# vA-ESP32.net
KiCad netlist of a schematic drawn in EAGLE
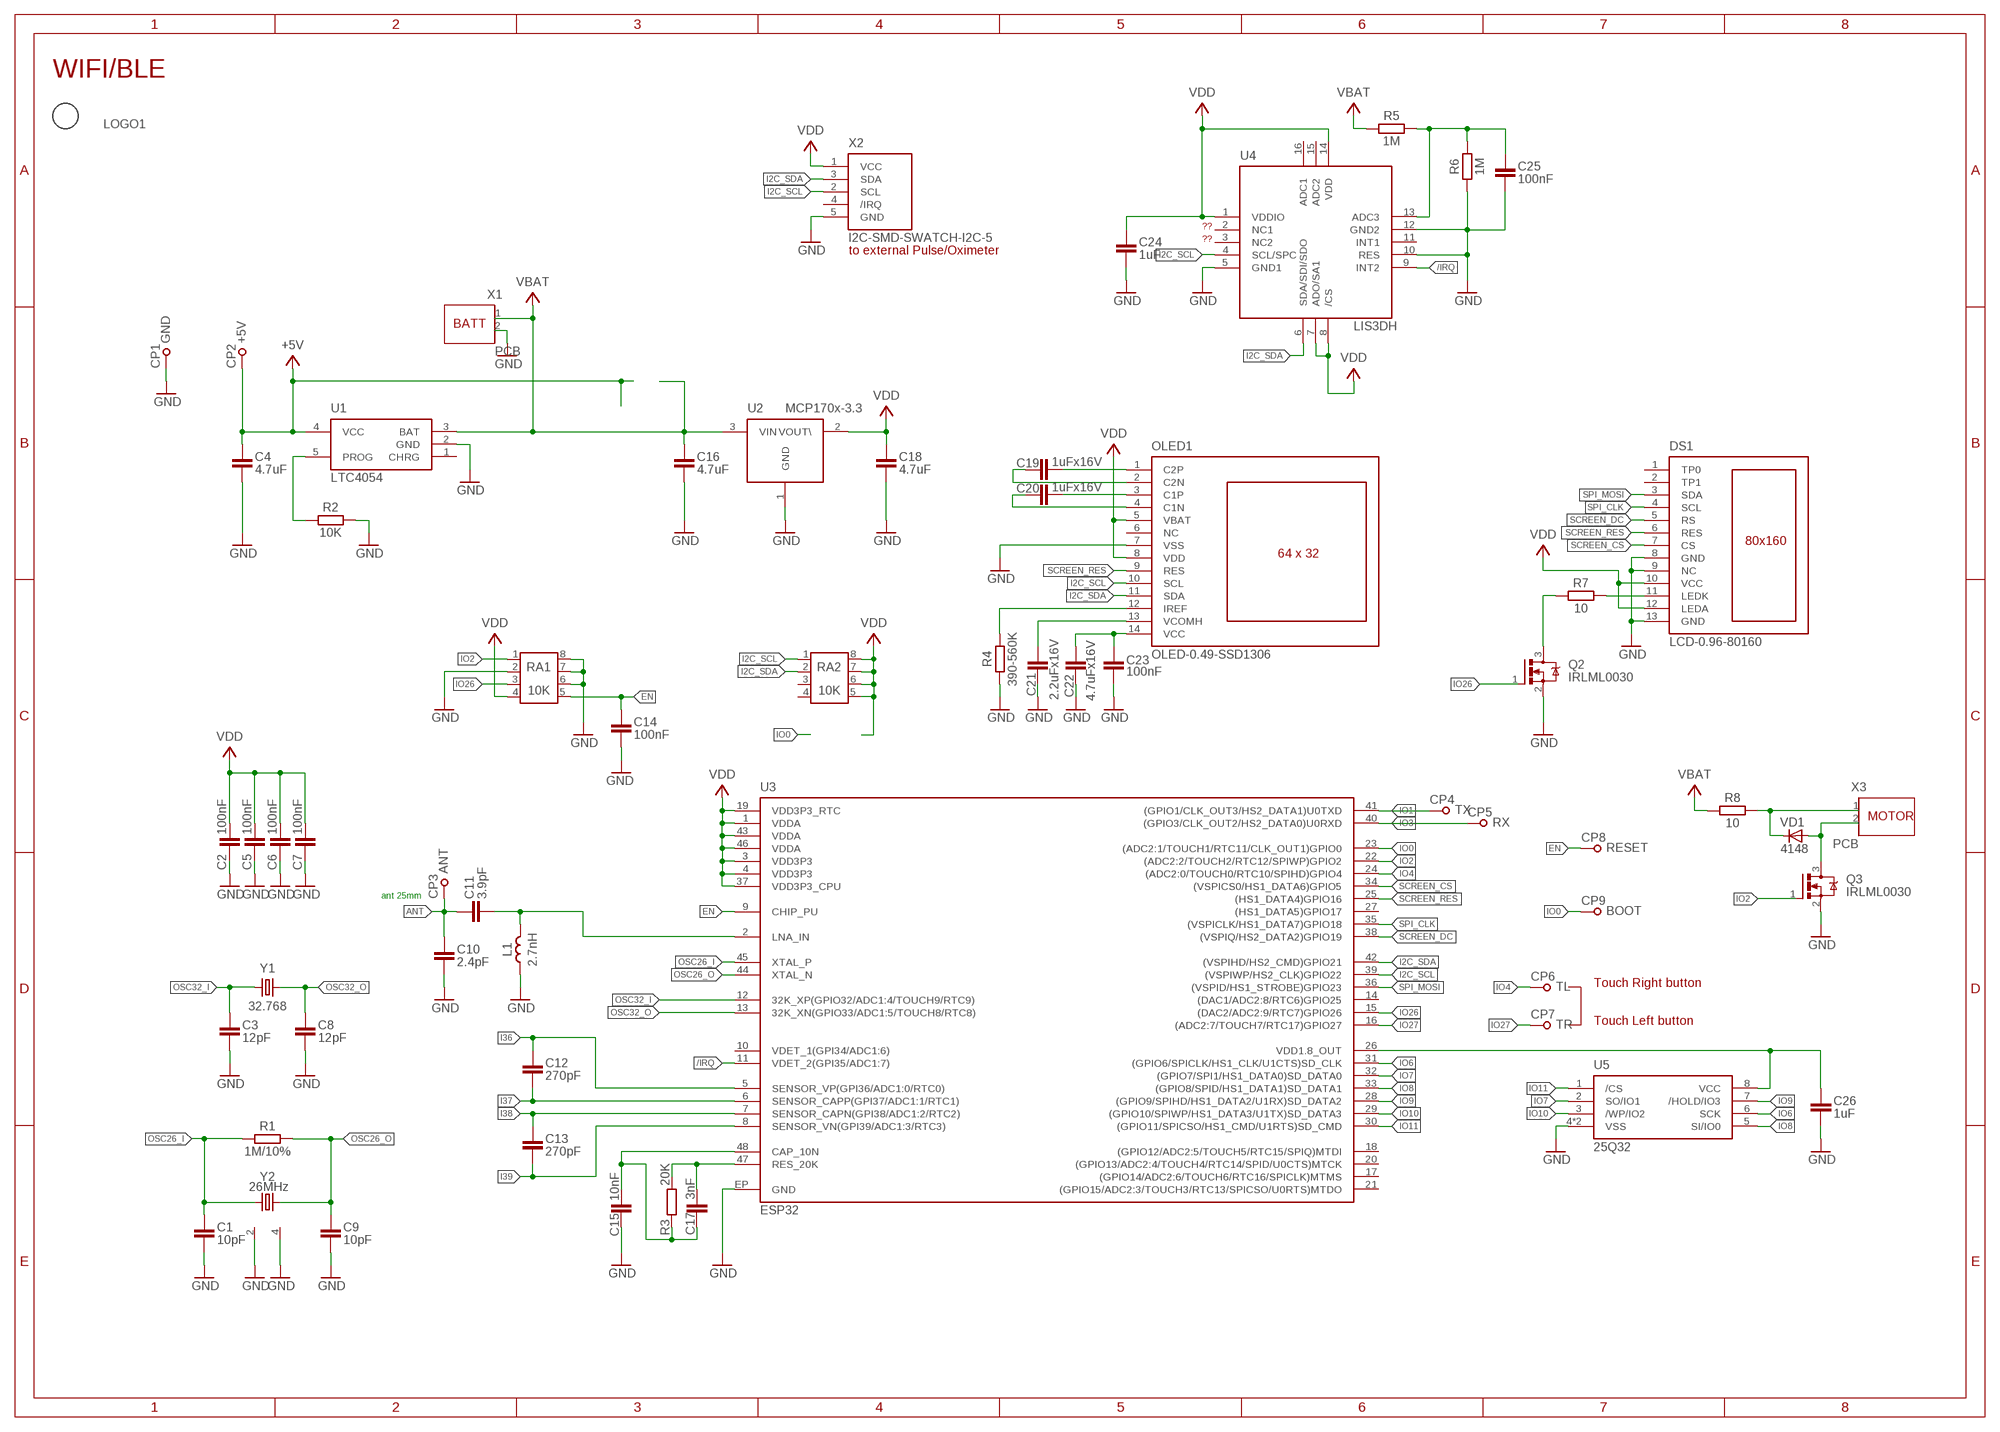
[diagram p0: schematic, sheet 1]

(export (version "E")
  (design (tool "Eeschema 10.0.6"))
  (components
    (comp (ref "C1")
      (value "10pF")
      (footprint "eagle-import:C0402")
      (libsource (lib "eagle-import") (part "C-EU-C0402"))
    )
    (comp (ref "C2")
      (value "100nF")
      (footprint "eagle-import:C0402")
      (libsource (lib "eagle-import") (part "C-EU-C0402"))
    )
    (comp (ref "C3")
      (value "12pF")
      (footprint "eagle-import:C0402")
      (libsource (lib "eagle-import") (part "C-EU-C0402"))
    )
    (comp (ref "C4")
      (value "4.7uF")
      (footprint "eagle-import:C0603")
      (libsource (lib "eagle-import") (part "C-EU-C0603"))
    )
    (comp (ref "C5")
      (value "100nF")
      (footprint "eagle-import:C0603")
      (libsource (lib "eagle-import") (part "C-EU-C0603"))
    )
    (comp (ref "C6")
      (value "100nF")
      (footprint "eagle-import:C0402")
      (libsource (lib "eagle-import") (part "C-EU-C0402"))
    )
    (comp (ref "C7")
      (value "100nF")
      (footprint "eagle-import:C0402")
      (libsource (lib "eagle-import") (part "C-EU-C0402"))
    )
    (comp (ref "C8")
      (value "12pF")
      (footprint "eagle-import:C0402")
      (libsource (lib "eagle-import") (part "C-EU-C0402"))
    )
    (comp (ref "C9")
      (value "10pF")
      (footprint "eagle-import:C0402")
      (libsource (lib "eagle-import") (part "C-EU-C0402"))
    )
    (comp (ref "C10")
      (value "2.4pF")
      (footprint "eagle-import:C0402")
      (libsource (lib "eagle-import") (part "C-EU-C0402"))
    )
    (comp (ref "C11")
      (value "3.9pF")
      (footprint "eagle-import:C0402")
      (libsource (lib "eagle-import") (part "C-EU-C0402"))
    )
    (comp (ref "C12")
      (value "270pF")
      (footprint "eagle-import:C0402")
      (libsource (lib "eagle-import") (part "C-EU-C0402"))
    )
    (comp (ref "C13")
      (value "270pF")
      (footprint "eagle-import:C0402")
      (libsource (lib "eagle-import") (part "C-EU-C0402"))
    )
    (comp (ref "C14")
      (value "100nF")
      (footprint "eagle-import:C0402")
      (libsource (lib "eagle-import") (part "C-EU-C0402"))
    )
    (comp (ref "C15")
      (value "10nF")
      (footprint "eagle-import:C0402")
      (libsource (lib "eagle-import") (part "C-EU-C0402"))
    )
    (comp (ref "C16")
      (value "4.7uF")
      (footprint "eagle-import:C0603")
      (libsource (lib "eagle-import") (part "C-EU-C0603"))
    )
    (comp (ref "C17")
      (value "3nF")
      (footprint "eagle-import:C0402")
      (libsource (lib "eagle-import") (part "C-EU-C0402"))
    )
    (comp (ref "C18")
      (value "4.7uF")
      (footprint "eagle-import:C0603")
      (libsource (lib "eagle-import") (part "C-EU-C0603"))
    )
    (comp (ref "C19")
      (value "1uFx16V")
      (footprint "eagle-import:C0603")
      (libsource (lib "eagle-import") (part "C-EU-C0603"))
    )
    (comp (ref "C20")
      (value "1uFx16V")
      (footprint "eagle-import:C0603")
      (libsource (lib "eagle-import") (part "C-EU-C0603"))
    )
    (comp (ref "C21")
      (value "2.2uFx16V")
      (footprint "eagle-import:C0805")
      (libsource (lib "eagle-import") (part "C-EU-C0805"))
    )
    (comp (ref "C22")
      (value "4.7uFx16V")
      (footprint "eagle-import:C0805")
      (libsource (lib "eagle-import") (part "C-EU-C0805"))
    )
    (comp (ref "C23")
      (value "100nF")
      (footprint "eagle-import:C0603")
      (libsource (lib "eagle-import") (part "C-EU-C0603"))
    )
    (comp (ref "C24")
      (value "1uF")
      (footprint "eagle-import:C0402")
      (libsource (lib "eagle-import") (part "C-EU-C0402"))
    )
    (comp (ref "C25")
      (value "100nF")
      (footprint "eagle-import:C0402")
      (libsource (lib "eagle-import") (part "C-EU-C0402"))
    )
    (comp (ref "C26")
      (value "1uF")
      (footprint "eagle-import:C0603")
      (libsource (lib "eagle-import") (part "C-EU-C0603"))
    )
    (comp (ref "CP1")
      (value "GND")
      (footprint "eagle-import:CP-1-R08MM")
      (libsource (lib "eagle-import") (part "CP-1"))
    )
    (comp (ref "CP2")
      (value "+5V")
      (footprint "eagle-import:CP-1-R08MM")
      (libsource (lib "eagle-import") (part "CP-1"))
    )
    (comp (ref "CP3")
      (value "ANT")
      (footprint "eagle-import:CP-1-C08MM")
      (libsource (lib "eagle-import") (part "CP"))
    )
    (comp (ref "CP4")
      (value "TX")
      (footprint "eagle-import:CP-1-C08MM")
      (libsource (lib "eagle-import") (part "CP"))
    )
    (comp (ref "CP5")
      (value "RX")
      (footprint "eagle-import:CP-1-C08MM")
      (libsource (lib "eagle-import") (part "CP"))
    )
    (comp (ref "CP6")
      (value "TL")
      (footprint "eagle-import:CP-1-C24MM")
      (libsource (lib "eagle-import") (part "CP-CP-1-C25"))
    )
    (comp (ref "CP7")
      (value "TR")
      (footprint "eagle-import:CP-1-C24MM")
      (libsource (lib "eagle-import") (part "CP-CP-1-C25"))
    )
    (comp (ref "CP8")
      (value "RESET")
      (footprint "eagle-import:CP-1-C08MM")
      (libsource (lib "eagle-import") (part "CP"))
    )
    (comp (ref "CP9")
      (value "BOOT")
      (footprint "eagle-import:CP-1-C08MM")
      (libsource (lib "eagle-import") (part "CP"))
    )
    (comp (ref "DS1")
      (value "LCD-0.96-80160")
      (footprint "eagle-import:LCD-0.96-80_160")
      (libsource (lib "eagle-import") (part "LCD-0.96-80160"))
    )
    (comp (ref "FIDUCIAL1")
      (value "FIDUCIAL-MICRO")
      (footprint "eagle-import:FIDUCIAL-MICRO")
      (libsource (lib "eagle-import") (part "FIDUCIAL-MICRO"))
    )
    (comp (ref "L1")
      (value "2.7nH")
      (footprint "eagle-import:L0402")
      (libsource (lib "eagle-import") (part "LL0402"))
    )
    (comp (ref "LOGO1")
      (value "LOGO6")
      (footprint "eagle-import:LOGO_OMEGA")
      (libsource (lib "eagle-import") (part "LOGO6"))
    )
    (comp (ref "OLED1")
      (value "OLED-0.49-SSD1306")
      (footprint "eagle-import:OLED_0.49-SSD1306")
      (libsource (lib "eagle-import") (part "OLED-0.49-SSD1306"))
    )
    (comp (ref "Q2")
      (value "IRLML0030")
      (footprint "eagle-import:SOT23-3-1")
      (libsource (lib "eagle-import") (part "FET_NSOT23"))
    )
    (comp (ref "Q3")
      (value "IRLML0030")
      (footprint "eagle-import:SOT23-3-1")
      (libsource (lib "eagle-import") (part "FET_NSOT23"))
    )
    (comp (ref "R1")
      (value "1M/10%")
      (footprint "eagle-import:R0402")
      (libsource (lib "eagle-import") (part "R-EU0402"))
    )
    (comp (ref "R2")
      (value "10K")
      (footprint "eagle-import:R0402")
      (libsource (lib "eagle-import") (part "R-EU0402"))
    )
    (comp (ref "R3")
      (value "20K")
      (footprint "eagle-import:R0402")
      (libsource (lib "eagle-import") (part "R-EU0402"))
    )
    (comp (ref "R4")
      (value "390-560K")
      (footprint "eagle-import:R0603")
      (libsource (lib "eagle-import") (part "R-EU0603"))
    )
    (comp (ref "R5")
      (value "1M")
      (footprint "eagle-import:R0402")
      (libsource (lib "eagle-import") (part "R-EU0402"))
    )
    (comp (ref "R6")
      (value "1M")
      (footprint "eagle-import:R0402")
      (libsource (lib "eagle-import") (part "R-EU0402"))
    )
    (comp (ref "R7")
      (value "10")
      (footprint "eagle-import:R0603")
      (libsource (lib "eagle-import") (part "R-EU0603"))
    )
    (comp (ref "R8")
      (value "10")
      (footprint "eagle-import:R0603")
      (libsource (lib "eagle-import") (part "R-EU0603"))
    )
    (comp (ref "RA1")
      (value "10K")
      (footprint "eagle-import:EXB28V")
      (libsource (lib "eagle-import") (part "R-ARRAY-4X0402"))
    )
    (comp (ref "RA2")
      (value "10K")
      (footprint "eagle-import:EXB28V")
      (libsource (lib "eagle-import") (part "R-ARRAY-4X0402"))
    )
    (comp (ref "U1")
      (value "LTC4054")
      (footprint "eagle-import:SOT23-5L")
      (libsource (lib "eagle-import") (part "LTC4054"))
    )
    (comp (ref "U2")
      (value "MCP170x-3.3")
      (footprint "eagle-import:SOT23-3")
      (libsource (lib "eagle-import") (part "MCP170XSOT23"))
    )
    (comp (ref "U3")
      (value "ESP32")
      (footprint "eagle-import:QFN48-6X6-0.4MM")
      (libsource (lib "eagle-import") (part "ESP32"))
    )
    (comp (ref "U4")
      (value "LIS3DH")
      (footprint "eagle-import:LGA16")
      (libsource (lib "eagle-import") (part "LIS3DH"))
    )
    (comp (ref "U5")
      (value "25Q32")
      (footprint "eagle-import:USON-8-2X3")
      (libsource (lib "eagle-import") (part "25CXX-USON8-2X3"))
    )
    (comp (ref "VD1")
      (value "4148")
      (footprint "eagle-import:SOD523")
      (libsource (lib "eagle-import") (part "DIODESOD523"))
    )
    (comp (ref "X1")
      (value "PCB")
      (footprint "eagle-import:2C_SMD-SWATCH")
      (libsource (lib "eagle-import") (part "CON-2PSMD-2"))
    )
    (comp (ref "X2")
      (value "I2C-SMD-SWATCH-I2C-5")
      (footprint "eagle-import:SMD-SWATCH-I2C-5")
      (libsource (lib "eagle-import") (part "I2C-SMD-SWATCH-I2C-5"))
    )
    (comp (ref "X3")
      (value "PCB")
      (footprint "eagle-import:2C_SMD-SWATCH")
      (libsource (lib "eagle-import") (part "CON-2PSMD-2"))
    )
    (comp (ref "Y1")
      (value "32.768")
      (footprint "eagle-import:XTAL3215")
      (libsource (lib "eagle-import") (part "REZONATOR-2PIN3215"))
    )
    (comp (ref "Y2")
      (value "26MHz")
      (footprint "eagle-import:CRYSTAL-SMD-3225")
      (libsource (lib "eagle-import") (part "REZONATOR-4PIN-3225"))
    )
  )
  (nets
    (net (code "1") (name "+5V") (class "Default")
      (node (ref "C4") (pin "1") (pinfunction "1_1") (pintype "passive"))
      (node (ref "CP2") (pin "1") (pinfunction "C1_1") (pintype "bidirectional"))
      (node (ref "U1") (pin "4") (pinfunction "VCC_4") (pintype "bidirectional"))
    )
    (net (code "2") (name "ANT") (class "Default")
      (node (ref "C10") (pin "1") (pinfunction "1_1") (pintype "passive"))
      (node (ref "C11") (pin "1") (pinfunction "1_1") (pintype "passive"))
      (node (ref "CP3") (pin "1") (pinfunction "C1_1") (pintype "bidirectional"))
    )
    (net (code "3") (name "EN") (class "Default")
      (node (ref "C14") (pin "1") (pinfunction "1_1") (pintype "passive"))
      (node (ref "CP8") (pin "1") (pinfunction "C1_1") (pintype "bidirectional"))
      (node (ref "RA1") (pin "5") (pinfunction "5_5") (pintype "passive"))
      (node (ref "U3") (pin "9") (pinfunction "CHIP_PU_9") (pintype "bidirectional"))
    )
    (net (code "4") (name "GND") (class "Default")
      (node (ref "C1") (pin "2") (pinfunction "2_2") (pintype "passive"))
      (node (ref "C10") (pin "2") (pinfunction "2_2") (pintype "passive"))
      (node (ref "C14") (pin "2") (pinfunction "2_2") (pintype "passive"))
      (node (ref "C15") (pin "2") (pinfunction "2_2") (pintype "passive"))
      (node (ref "C16") (pin "2") (pinfunction "2_2") (pintype "passive"))
      (node (ref "C18") (pin "2") (pinfunction "2_2") (pintype "passive"))
      (node (ref "C2") (pin "2") (pinfunction "2_2") (pintype "passive"))
      (node (ref "C21") (pin "2") (pinfunction "2_2") (pintype "passive"))
      (node (ref "C22") (pin "2") (pinfunction "2_2") (pintype "passive"))
      (node (ref "C23") (pin "2") (pinfunction "2_2") (pintype "passive"))
      (node (ref "C24") (pin "2") (pinfunction "2_2") (pintype "passive"))
      (node (ref "C25") (pin "2") (pinfunction "2_2") (pintype "passive"))
      (node (ref "C26") (pin "2") (pinfunction "2_2") (pintype "passive"))
      (node (ref "C3") (pin "2") (pinfunction "2_2") (pintype "passive"))
      (node (ref "C4") (pin "2") (pinfunction "2_2") (pintype "passive"))
      (node (ref "C5") (pin "2") (pinfunction "2_2") (pintype "passive"))
      (node (ref "C6") (pin "2") (pinfunction "2_2") (pintype "passive"))
      (node (ref "C7") (pin "2") (pinfunction "2_2") (pintype "passive"))
      (node (ref "C8") (pin "2") (pinfunction "2_2") (pintype "passive"))
      (node (ref "C9") (pin "2") (pinfunction "2_2") (pintype "passive"))
      (node (ref "CP1") (pin "1") (pinfunction "C1_1") (pintype "bidirectional"))
      (node (ref "DS1") (pin "13") (pinfunction "GND_13") (pintype "bidirectional"))
      (node (ref "DS1") (pin "8") (pinfunction "GND_8") (pintype "bidirectional"))
      (node (ref "DS1") (pin "9") (pinfunction "NC_9") (pintype "bidirectional"))
      (node (ref "L1") (pin "1") (pinfunction "%1_1") (pintype "bidirectional"))
      (node (ref "OLED1") (pin "7") (pinfunction "VSS_7") (pintype "bidirectional"))
      (node (ref "Q2") (pin "2") (pinfunction "S_2") (pintype "passive"))
      (node (ref "Q3") (pin "2") (pinfunction "S_2") (pintype "passive"))
      (node (ref "R2") (pin "2") (pinfunction "2_2") (pintype "passive"))
      (node (ref "R4") (pin "1") (pinfunction "1_1") (pintype "passive"))
      (node (ref "R6") (pin "1") (pinfunction "1_1") (pintype "passive"))
      (node (ref "RA1") (pin "2") (pinfunction "2_2") (pintype "passive"))
      (node (ref "RA1") (pin "6") (pinfunction "6_6") (pintype "passive"))
      (node (ref "RA1") (pin "7") (pinfunction "7_7") (pintype "passive"))
      (node (ref "RA1") (pin "8") (pinfunction "8_8") (pintype "passive"))
      (node (ref "U1") (pin "2") (pinfunction "GND_2") (pintype "bidirectional"))
      (node (ref "U2") (pin "1") (pinfunction "GND_1") (pintype "bidirectional"))
      (node (ref "U3") (pin "EP") (pinfunction "GND_EP") (pintype "bidirectional"))
      (node (ref "U4") (pin "10") (pinfunction "RES_10") (pintype "bidirectional"))
      (node (ref "U4") (pin "12") (pinfunction "GND2_12") (pintype "bidirectional"))
      (node (ref "U4") (pin "5") (pinfunction "GND1_5") (pintype "bidirectional"))
      (node (ref "U5") (pin "4") (pinfunction "VSS_4") (pintype "bidirectional"))
      (node (ref "U5") (pin "P$1") (pinfunction "VSS_P$1") (pintype "bidirectional"))
      (node (ref "X1") (pin "2") (pinfunction "2_2") (pintype "bidirectional"))
      (node (ref "X2") (pin "5") (pinfunction "GND_5") (pintype "bidirectional"))
      (node (ref "Y2") (pin "2") (pinfunction "S_2") (pintype "bidirectional"))
      (node (ref "Y2") (pin "4") (pinfunction "S_4") (pintype "bidirectional"))
    )
    (net (code "5") (name "I2C_SCL") (class "Default")
      (node (ref "OLED1") (pin "10") (pinfunction "SCL_10") (pintype "bidirectional"))
      (node (ref "RA2") (pin "1") (pinfunction "1_1") (pintype "passive"))
      (node (ref "U3") (pin "39") (pinfunction "(VSPIWP/HS2_CLK)GPIO22_39") (pintype "bidirectional"))
      (node (ref "U4") (pin "4") (pinfunction "SCL/SPC_4") (pintype "bidirectional"))
      (node (ref "X2") (pin "2") (pinfunction "SCL_2") (pintype "bidirectional"))
    )
    (net (code "6") (name "I2C_SDA") (class "Default")
      (node (ref "OLED1") (pin "11") (pinfunction "SDA_11") (pintype "bidirectional"))
      (node (ref "RA2") (pin "2") (pinfunction "2_2") (pintype "passive"))
      (node (ref "U3") (pin "42") (pinfunction "(VSPIHD/HS2_CMD)GPIO21_42") (pintype "bidirectional"))
      (node (ref "U4") (pin "6") (pinfunction "SDA/SDI/SDO_6") (pintype "bidirectional"))
      (node (ref "X2") (pin "3") (pinfunction "SDA_3") (pintype "bidirectional"))
    )
    (net (code "7") (name "I36") (class "Default")
      (node (ref "C12") (pin "1") (pinfunction "1_1") (pintype "passive"))
      (node (ref "U3") (pin "5") (pinfunction "SENSOR_VP(GPI36/ADC1:0/RTC0)_5") (pintype "bidirectional"))
    )
    (net (code "8") (name "I37") (class "Default")
      (node (ref "C12") (pin "2") (pinfunction "2_2") (pintype "passive"))
      (node (ref "U3") (pin "6") (pinfunction "SENSOR_CAPP(GPI37/ADC1:1/RTC1)_6") (pintype "bidirectional"))
    )
    (net (code "9") (name "I38") (class "Default")
      (node (ref "C13") (pin "1") (pinfunction "1_1") (pintype "passive"))
      (node (ref "U3") (pin "7") (pinfunction "SENSOR_CAPN(GPI38/ADC1:2/RTC2)_7") (pintype "bidirectional"))
    )
    (net (code "10") (name "I39") (class "Default")
      (node (ref "C13") (pin "2") (pinfunction "2_2") (pintype "passive"))
      (node (ref "U3") (pin "8") (pinfunction "SENSOR_VN(GPI39/ADC1:3/RTC3)_8") (pintype "bidirectional"))
    )
    (net (code "11") (name "IO0") (class "Default")
      (node (ref "CP9") (pin "1") (pinfunction "C1_1") (pintype "bidirectional"))
      (node (ref "U3") (pin "23") (pinfunction "(ADC2:1/TOUCH1/RTC11/CLK_OUT1)GPIO0_23") (pintype "bidirectional"))
    )
    (net (code "12") (name "IO1") (class "Default")
      (node (ref "CP4") (pin "1") (pinfunction "C1_1") (pintype "bidirectional"))
      (node (ref "U3") (pin "41") (pinfunction "(GPIO1/CLK_OUT3/HS2_DATA1)U0TXD_41") (pintype "bidirectional"))
    )
    (net (code "13") (name "IO2") (class "Default")
      (node (ref "Q3") (pin "1") (pinfunction "G_1") (pintype "passive"))
      (node (ref "RA1") (pin "1") (pinfunction "1_1") (pintype "passive"))
      (node (ref "U3") (pin "22") (pinfunction "(ADC2:2/TOUCH2/RTC12/SPIWP)GPIO2_22") (pintype "bidirectional"))
    )
    (net (code "14") (name "IO3") (class "Default")
      (node (ref "CP5") (pin "1") (pinfunction "C1_1") (pintype "bidirectional"))
      (node (ref "U3") (pin "40") (pinfunction "(GPIO3/CLK_OUT2/HS2_DATA0)U0RXD_40") (pintype "bidirectional"))
    )
    (net (code "15") (name "IO4") (class "Default")
      (node (ref "CP6") (pin "1") (pinfunction "C1_1") (pintype "bidirectional"))
      (node (ref "U3") (pin "24") (pinfunction "(ADC2:0/TOUCH0/RTC10/SPIHD)GPIO4_24") (pintype "bidirectional"))
    )
    (net (code "16") (name "IO6") (class "Default")
      (node (ref "U3") (pin "31") (pinfunction "(GPIO6/SPICLK/HS1_CLK/U1CTS)SD_CLK_31") (pintype "bidirectional"))
      (node (ref "U5") (pin "6") (pinfunction "SCK_6") (pintype "bidirectional"))
    )
    (net (code "17") (name "IO7") (class "Default")
      (node (ref "U3") (pin "32") (pinfunction "(GPIO7/SPI1/HS1_DATA0)SD_DATA0_32") (pintype "bidirectional"))
      (node (ref "U5") (pin "2") (pinfunction "SO/IO1_2") (pintype "bidirectional"))
    )
    (net (code "18") (name "IO8") (class "Default")
      (node (ref "U3") (pin "33") (pinfunction "(GPIO8/SPID/HS1_DATA1)SD_DATA1_33") (pintype "bidirectional"))
      (node (ref "U5") (pin "5") (pinfunction "SI/IO0_5") (pintype "bidirectional"))
    )
    (net (code "19") (name "IO9") (class "Default")
      (node (ref "U3") (pin "28") (pinfunction "(GPIO9/SPIHD/HS1_DATA2/U1RX)SD_DATA2_28") (pintype "bidirectional"))
      (node (ref "U5") (pin "7") (pinfunction "/HOLD/IO3_7") (pintype "bidirectional"))
    )
    (net (code "20") (name "IO10") (class "Default")
      (node (ref "U3") (pin "29") (pinfunction "(GPIO10/SPIWP/HS1_DATA3/U1TX)SD_DATA3_29") (pintype "bidirectional"))
      (node (ref "U5") (pin "3") (pinfunction "/WP/IO2_3") (pintype "bidirectional"))
    )
    (net (code "21") (name "IO11") (class "Default")
      (node (ref "U3") (pin "30") (pinfunction "(GPIO11/SPICSO/HS1_CMD/U1RTS)SD_CMD_30") (pintype "bidirectional"))
      (node (ref "U5") (pin "1") (pinfunction "/CS_1") (pintype "bidirectional"))
    )
    (net (code "22") (name "IO26") (class "Default")
      (node (ref "Q2") (pin "1") (pinfunction "G_1") (pintype "passive"))
      (node (ref "RA1") (pin "3") (pinfunction "3_3") (pintype "passive"))
      (node (ref "U3") (pin "15") (pinfunction "(DAC2/ADC2:9/RTC7)GPIO26_15") (pintype "bidirectional"))
    )
    (net (code "23") (name "IO27") (class "Default")
      (node (ref "CP7") (pin "1") (pinfunction "C1_1") (pintype "bidirectional"))
      (node (ref "U3") (pin "16") (pinfunction "(ADC2:7/TOUCH7/RTC17)GPIO27_16") (pintype "bidirectional"))
    )
    (net (code "24") (name "Net-(DS1-LEDK)") (class "Default")
      (node (ref "DS1") (pin "11") (pinfunction "LEDK_11") (pintype "bidirectional"))
      (node (ref "R7") (pin "2") (pinfunction "2_2") (pintype "passive"))
    )
    (net (code "25") (name "Net-(L1-%2)") (class "Default")
      (node (ref "C11") (pin "2") (pinfunction "2_2") (pintype "passive"))
      (node (ref "L1") (pin "2") (pinfunction "%2_2") (pintype "bidirectional"))
      (node (ref "U3") (pin "2") (pinfunction "LNA_IN_2") (pintype "bidirectional"))
    )
    (net (code "26") (name "Net-(OLED1-C1N)") (class "Default")
      (node (ref "C20") (pin "1") (pinfunction "1_1") (pintype "passive"))
      (node (ref "OLED1") (pin "4") (pinfunction "C1N_4") (pintype "bidirectional"))
    )
    (net (code "27") (name "Net-(OLED1-C1P)") (class "Default")
      (node (ref "C20") (pin "2") (pinfunction "2_2") (pintype "passive"))
      (node (ref "OLED1") (pin "3") (pinfunction "C1P_3") (pintype "bidirectional"))
    )
    (net (code "28") (name "Net-(OLED1-C2N)") (class "Default")
      (node (ref "C19") (pin "1") (pinfunction "1_1") (pintype "passive"))
      (node (ref "OLED1") (pin "2") (pinfunction "C2N_2") (pintype "bidirectional"))
    )
    (net (code "29") (name "Net-(OLED1-C2P)") (class "Default")
      (node (ref "C19") (pin "2") (pinfunction "2_2") (pintype "passive"))
      (node (ref "OLED1") (pin "1") (pinfunction "C2P_1") (pintype "bidirectional"))
    )
    (net (code "30") (name "Net-(OLED1-IREF)") (class "Default")
      (node (ref "OLED1") (pin "12") (pinfunction "IREF_12") (pintype "bidirectional"))
      (node (ref "R4") (pin "2") (pinfunction "2_2") (pintype "passive"))
    )
    (net (code "31") (name "Net-(OLED1-VCC)") (class "Default")
      (node (ref "C22") (pin "1") (pinfunction "1_1") (pintype "passive"))
      (node (ref "C23") (pin "1") (pinfunction "1_1") (pintype "passive"))
      (node (ref "OLED1") (pin "14") (pinfunction "VCC_14") (pintype "bidirectional"))
    )
    (net (code "32") (name "Net-(OLED1-VCOMH)") (class "Default")
      (node (ref "C21") (pin "1") (pinfunction "1_1") (pintype "passive"))
      (node (ref "OLED1") (pin "13") (pinfunction "VCOMH_13") (pintype "bidirectional"))
    )
    (net (code "33") (name "Net-(Q2-D)") (class "Default")
      (node (ref "Q2") (pin "3") (pinfunction "D_3") (pintype "passive"))
      (node (ref "R7") (pin "1") (pinfunction "1_1") (pintype "passive"))
    )
    (net (code "34") (name "Net-(Q3-D)") (class "Default")
      (node (ref "Q3") (pin "3") (pinfunction "D_3") (pintype "passive"))
      (node (ref "VD1") (pin "A") (pinfunction "A_A") (pintype "passive"))
      (node (ref "X3") (pin "2") (pinfunction "2_2") (pintype "bidirectional"))
    )
    (net (code "35") (name "Net-(R8-Pad2)") (class "Default")
      (node (ref "R8") (pin "2") (pinfunction "2_2") (pintype "passive"))
      (node (ref "VD1") (pin "C") (pinfunction "C_C") (pintype "passive"))
      (node (ref "X3") (pin "1") (pinfunction "1_1") (pintype "bidirectional"))
    )
    (net (code "36") (name "Net-(U1-PROG)") (class "Default")
      (node (ref "R2") (pin "1") (pinfunction "1_1") (pintype "passive"))
      (node (ref "U1") (pin "5") (pinfunction "PROG_5") (pintype "bidirectional"))
    )
    (net (code "37") (name "Net-(U3-CAP_10N)") (class "Default")
      (node (ref "C15") (pin "1") (pinfunction "1_1") (pintype "passive"))
      (node (ref "C17") (pin "2") (pinfunction "2_2") (pintype "passive"))
      (node (ref "R3") (pin "2") (pinfunction "2_2") (pintype "passive"))
      (node (ref "U3") (pin "48") (pinfunction "CAP_10N_48") (pintype "bidirectional"))
    )
    (net (code "38") (name "Net-(U3-RES_20K)") (class "Default")
      (node (ref "C17") (pin "1") (pinfunction "1_1") (pintype "passive"))
      (node (ref "R3") (pin "1") (pinfunction "1_1") (pintype "passive"))
      (node (ref "U3") (pin "47") (pinfunction "RES_20K_47") (pintype "bidirectional"))
    )
    (net (code "39") (name "Net-(U3-VDD1.8_OUT)") (class "Default")
      (node (ref "C26") (pin "1") (pinfunction "1_1") (pintype "passive"))
      (node (ref "U3") (pin "26") (pinfunction "VDD1.8_OUT_26") (pintype "bidirectional"))
      (node (ref "U5") (pin "8") (pinfunction "VCC_8") (pintype "bidirectional"))
    )
    (net (code "40") (name "Net-(U4-ADC3)") (class "Default")
      (node (ref "C25") (pin "1") (pinfunction "1_1") (pintype "passive"))
      (node (ref "R5") (pin "2") (pinfunction "2_2") (pintype "passive"))
      (node (ref "R6") (pin "2") (pinfunction "2_2") (pintype "passive"))
      (node (ref "U4") (pin "13") (pinfunction "ADC3_13") (pintype "bidirectional"))
    )
    (net (code "41") (name "OSC26_I") (class "Default")
      (node (ref "C1") (pin "1") (pinfunction "1_1") (pintype "passive"))
      (node (ref "R1") (pin "1") (pinfunction "1_1") (pintype "passive"))
      (node (ref "U3") (pin "45") (pinfunction "XTAL_P_45") (pintype "bidirectional"))
      (node (ref "Y2") (pin "1") (pinfunction "1_1") (pintype "passive"))
    )
    (net (code "42") (name "OSC26_O") (class "Default")
      (node (ref "C9") (pin "1") (pinfunction "1_1") (pintype "passive"))
      (node (ref "R1") (pin "2") (pinfunction "2_2") (pintype "passive"))
      (node (ref "U3") (pin "44") (pinfunction "XTAL_N_44") (pintype "bidirectional"))
      (node (ref "Y2") (pin "3") (pinfunction "2_3") (pintype "passive"))
    )
    (net (code "43") (name "OSC32_I") (class "Default")
      (node (ref "C3") (pin "1") (pinfunction "1_1") (pintype "passive"))
      (node (ref "U3") (pin "12") (pinfunction "32K_XP(GPIO32/ADC1:4/TOUCH9/RTC9)_12") (pintype "bidirectional"))
      (node (ref "Y1") (pin "1") (pinfunction "1_1") (pintype "passive"))
    )
    (net (code "44") (name "OSC32_O") (class "Default")
      (node (ref "C8") (pin "1") (pinfunction "1_1") (pintype "passive"))
      (node (ref "U3") (pin "13") (pinfunction "32K_XN(GPIO33/ADC1:5/TOUCH8/RTC8)_13") (pintype "bidirectional"))
      (node (ref "Y1") (pin "2") (pinfunction "2_2") (pintype "passive"))
    )
    (net (code "45") (name "SCREEN_CS") (class "Default")
      (node (ref "DS1") (pin "7") (pinfunction "CS_7") (pintype "bidirectional"))
      (node (ref "U3") (pin "34") (pinfunction "(VSPICS0/HS1_DATA6)GPIO5_34") (pintype "bidirectional"))
    )
    (net (code "46") (name "SCREEN_DC") (class "Default")
      (node (ref "DS1") (pin "5") (pinfunction "RS_5") (pintype "bidirectional"))
      (node (ref "U3") (pin "38") (pinfunction "(VSPIQ/HS2_DATA2)GPIO19_38") (pintype "bidirectional"))
    )
    (net (code "47") (name "SCREEN_RES") (class "Default")
      (node (ref "DS1") (pin "6") (pinfunction "RES_6") (pintype "bidirectional"))
      (node (ref "OLED1") (pin "9") (pinfunction "RES_9") (pintype "bidirectional"))
      (node (ref "U3") (pin "25") (pinfunction "(HS1_DATA4)GPIO16_25") (pintype "bidirectional"))
    )
    (net (code "48") (name "SPI_CLK") (class "Default")
      (node (ref "DS1") (pin "4") (pinfunction "SCL_4") (pintype "bidirectional"))
      (node (ref "U3") (pin "35") (pinfunction "(VSPICLK/HS1_DATA7)GPIO18_35") (pintype "bidirectional"))
    )
    (net (code "49") (name "SPI_MOSI") (class "Default")
      (node (ref "DS1") (pin "3") (pinfunction "SDA_3") (pintype "bidirectional"))
      (node (ref "U3") (pin "36") (pinfunction "(VSPID/HS1_STROBE)GPIO23_36") (pintype "bidirectional"))
    )
    (net (code "50") (name "VBAT") (class "Default")
      (node (ref "C16") (pin "1") (pinfunction "1_1") (pintype "passive"))
      (node (ref "R5") (pin "1") (pinfunction "1_1") (pintype "passive"))
      (node (ref "R8") (pin "1") (pinfunction "1_1") (pintype "passive"))
      (node (ref "U1") (pin "3") (pinfunction "BAT_3") (pintype "bidirectional"))
      (node (ref "U2") (pin "3") (pinfunction "VIN_3") (pintype "bidirectional"))
      (node (ref "X1") (pin "1") (pinfunction "1_1") (pintype "bidirectional"))
    )
    (net (code "51") (name "VDD") (class "Default")
      (node (ref "C18") (pin "1") (pinfunction "1_1") (pintype "passive"))
      (node (ref "C2") (pin "1") (pinfunction "1_1") (pintype "passive"))
      (node (ref "C24") (pin "1") (pinfunction "1_1") (pintype "passive"))
      (node (ref "C5") (pin "1") (pinfunction "1_1") (pintype "passive"))
      (node (ref "C6") (pin "1") (pinfunction "1_1") (pintype "passive"))
      (node (ref "C7") (pin "1") (pinfunction "1_1") (pintype "passive"))
      (node (ref "DS1") (pin "10") (pinfunction "VCC_10") (pintype "bidirectional"))
      (node (ref "DS1") (pin "12") (pinfunction "LEDA_12") (pintype "bidirectional"))
      (node (ref "OLED1") (pin "5") (pinfunction "VBAT_5") (pintype "bidirectional"))
      (node (ref "OLED1") (pin "8") (pinfunction "VDD_8") (pintype "bidirectional"))
      (node (ref "RA1") (pin "4") (pinfunction "4_4") (pintype "passive"))
      (node (ref "RA2") (pin "5") (pinfunction "5_5") (pintype "passive"))
      (node (ref "RA2") (pin "6") (pinfunction "6_6") (pintype "passive"))
      (node (ref "RA2") (pin "7") (pinfunction "7_7") (pintype "passive"))
      (node (ref "RA2") (pin "8") (pinfunction "8_8") (pintype "passive"))
      (node (ref "U2") (pin "2") (pinfunction "VOUT\\_2") (pintype "bidirectional"))
      (node (ref "U3") (pin "1") (pinfunction "VDDA_1") (pintype "bidirectional"))
      (node (ref "U3") (pin "19") (pinfunction "VDD3P3_RTC_19") (pintype "bidirectional"))
      (node (ref "U3") (pin "3") (pinfunction "VDD3P3_3") (pintype "bidirectional"))
      (node (ref "U3") (pin "37") (pinfunction "VDD3P3_CPU_37") (pintype "bidirectional"))
      (node (ref "U3") (pin "4") (pinfunction "VDD3P3_4") (pintype "bidirectional"))
      (node (ref "U3") (pin "43") (pinfunction "VDDA_43") (pintype "bidirectional"))
      (node (ref "U3") (pin "46") (pinfunction "VDDA_46") (pintype "bidirectional"))
      (node (ref "U4") (pin "1") (pinfunction "VDDIO_1") (pintype "bidirectional"))
      (node (ref "U4") (pin "14") (pinfunction "VDD_14") (pintype "bidirectional"))
      (node (ref "U4") (pin "7") (pinfunction "ADO/SA1_7") (pintype "bidirectional"))
      (node (ref "U4") (pin "8") (pinfunction "/CS_8") (pintype "bidirectional"))
      (node (ref "X2") (pin "1") (pinfunction "VCC_1") (pintype "bidirectional"))
    )
    (net (code "52") (name "unconnected-(DS1-TP0-Pad1)") (class "Default")
      (node (ref "DS1") (pin "1") (pinfunction "TP0_1") (pintype "bidirectional"))
    )
    (net (code "53") (name "unconnected-(DS1-TP1-Pad2)") (class "Default")
      (node (ref "DS1") (pin "2") (pinfunction "TP1_2") (pintype "bidirectional"))
    )
    (net (code "54") (name "unconnected-(OLED1-NC-Pad6)") (class "Default")
      (node (ref "OLED1") (pin "6") (pinfunction "NC_6") (pintype "bidirectional"))
    )
    (net (code "55") (name "unconnected-(RA2-Pad3)") (class "Default")
      (node (ref "RA2") (pin "3") (pinfunction "3_3") (pintype "passive"))
    )
    (net (code "56") (name "unconnected-(RA2-Pad4)") (class "Default")
      (node (ref "RA2") (pin "4") (pinfunction "4_4") (pintype "passive"))
    )
    (net (code "57") (name "unconnected-(U1-CHRG-Pad1)") (class "Default")
      (node (ref "U1") (pin "1") (pinfunction "CHRG_1") (pintype "bidirectional"))
    )
    (net (code "58") (name "unconnected-(U3-(DAC1{slash}ADC2:8{slash}RTC6)GPIO25-Pad14)") (class "Default")
      (node (ref "U3") (pin "14") (pinfunction "(DAC1/ADC2:8/RTC6)GPIO25_14") (pintype "bidirectional"))
    )
    (net (code "59") (name "unconnected-(U3-(GPIO12{slash}ADC2:5{slash}TOUCH5{slash}RTC15{slash}SPIQ)MTDI-Pad18)") (class "Default")
      (node (ref "U3") (pin "18") (pinfunction "(GPIO12/ADC2:5/TOUCH5/RTC15/SPIQ)MTDI_18") (pintype "bidirectional"))
    )
    (net (code "60") (name "unconnected-(U3-(GPIO13{slash}ADC2:4{slash}TOUCH4{slash}RTC14{slash}SPID{slash}U0CTS)MTCK-Pad20)") (class "Default")
      (node (ref "U3") (pin "20") (pinfunction "(GPIO13/ADC2:4/TOUCH4/RTC14/SPID/U0CTS)MTCK_20") (pintype "bidirectional"))
    )
    (net (code "61") (name "unconnected-(U3-(GPIO14{slash}ADC2:6{slash}TOUCH6{slash}RTC16{slash}SPICLK)MTMS-Pad17)") (class "Default")
      (node (ref "U3") (pin "17") (pinfunction "(GPIO14/ADC2:6/TOUCH6/RTC16/SPICLK)MTMS_17") (pintype "bidirectional"))
    )
    (net (code "62") (name "unconnected-(U3-(GPIO15{slash}ADC2:3{slash}TOUCH3{slash}RTC13{slash}SPICSO{slash}U0RTS)MTDO-Pad21)") (class "Default")
      (node (ref "U3") (pin "21") (pinfunction "(GPIO15/ADC2:3/TOUCH3/RTC13/SPICSO/U0RTS)MTDO_21") (pintype "bidirectional"))
    )
    (net (code "63") (name "unconnected-(U3-(HS1_DATA5)GPIO17-Pad27)") (class "Default")
      (node (ref "U3") (pin "27") (pinfunction "(HS1_DATA5)GPIO17_27") (pintype "bidirectional"))
    )
    (net (code "64") (name "unconnected-(U3-VDET_1(GPI34{slash}ADC1:6)-Pad10)") (class "Default")
      (node (ref "U3") (pin "10") (pinfunction "VDET_1(GPI34/ADC1:6)_10") (pintype "bidirectional"))
    )
    (net (code "65") (name "unconnected-(U4-ADC1-Pad16)") (class "Default")
      (node (ref "U4") (pin "16") (pinfunction "ADC1_16") (pintype "bidirectional"))
    )
    (net (code "66") (name "unconnected-(U4-ADC2-Pad15)") (class "Default")
      (node (ref "U4") (pin "15") (pinfunction "ADC2_15") (pintype "bidirectional"))
    )
    (net (code "67") (name "unconnected-(U4-INT1-Pad11)") (class "Default")
      (node (ref "U4") (pin "11") (pinfunction "INT1_11") (pintype "bidirectional"))
    )
    (net (code "68") (name "unconnected-(U4-NC1-Pad2)") (class "Default")
      (node (ref "U4") (pin "2") (pinfunction "NC1_2") (pintype "bidirectional"))
    )
    (net (code "69") (name "unconnected-(U4-NC2-Pad3)") (class "Default")
      (node (ref "U4") (pin "3") (pinfunction "NC2_3") (pintype "bidirectional"))
    )
    (net (code "70") (name "unconnected-(X2-{slash}IRQ-Pad4)") (class "Default")
      (node (ref "X2") (pin "4") (pinfunction "/IRQ_4") (pintype "bidirectional"))
    )
    (net (code "71") (name "{slash}IRQ") (class "Default")
      (node (ref "U3") (pin "11") (pinfunction "VDET_2(GPI35/ADC1:7)_11") (pintype "bidirectional"))
      (node (ref "U4") (pin "9") (pinfunction "INT2_9") (pintype "bidirectional"))
    )
  )
)
